# robot.net
KiCad netlist of a schematic drawn in EAGLE
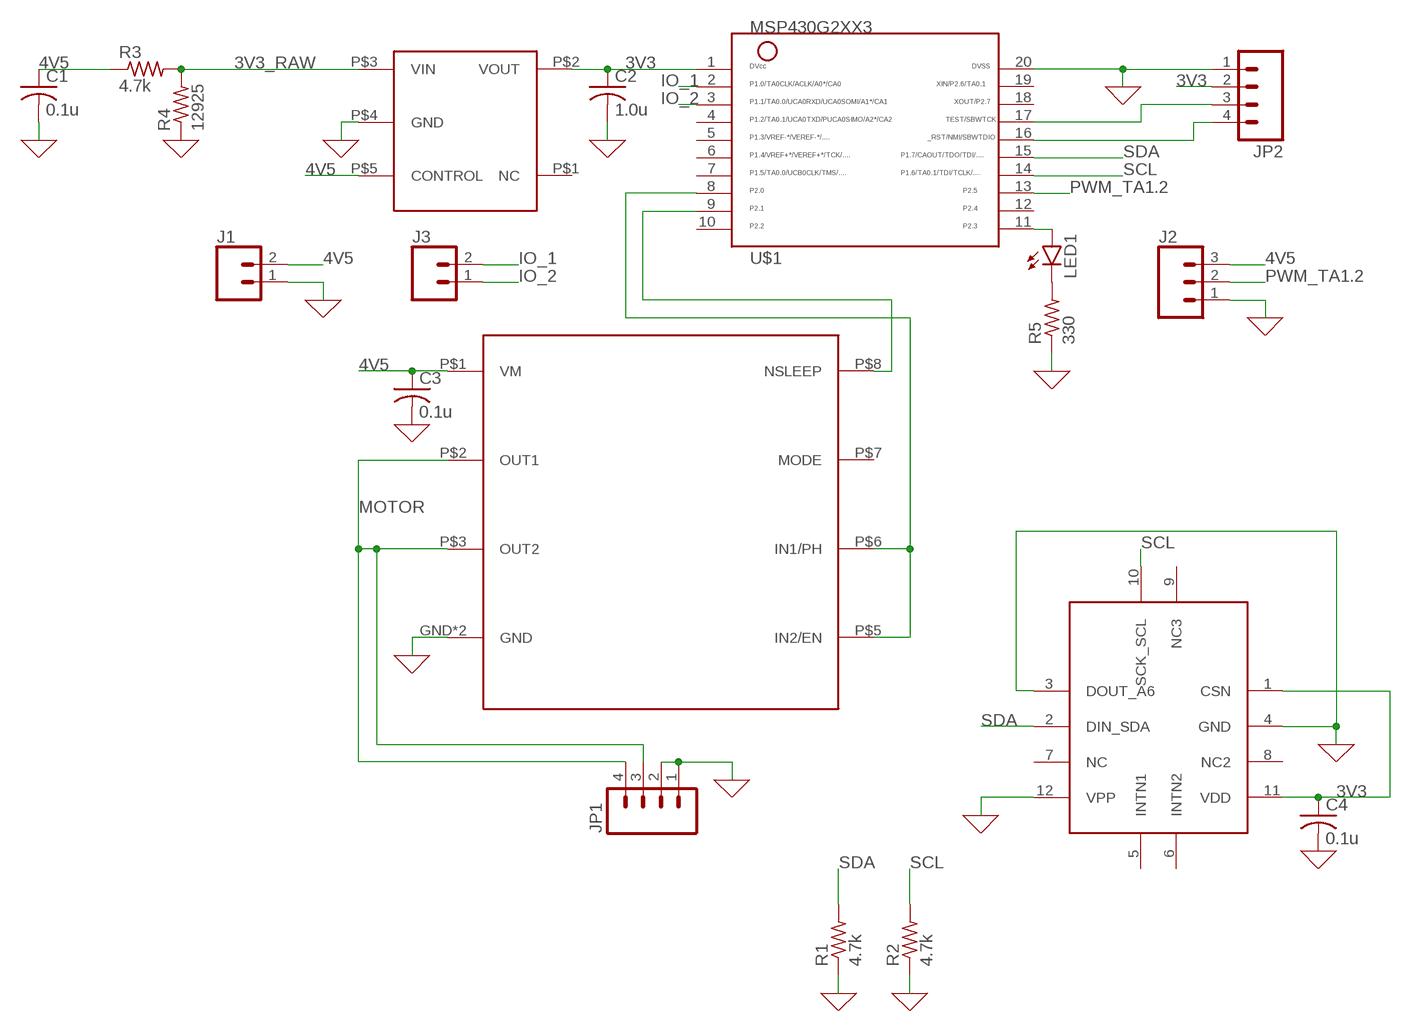
[diagram p0: schematic, sheet 1]

(export (version "E")
  (design (tool "Eeschema 10.0.6"))
  (components
    (comp (ref "C1")
      (value "0.1u")
      (footprint "eagle-import:C0805")
      (libsource (lib "eagle-import") (part "C-USC0805"))
    )
    (comp (ref "C2")
      (value "1.0u")
      (footprint "eagle-import:C0805")
      (libsource (lib "eagle-import") (part "C-USC0805"))
    )
    (comp (ref "C3")
      (value "0.1u")
      (footprint "eagle-import:C0805")
      (libsource (lib "eagle-import") (part "C-USC0805"))
    )
    (comp (ref "C4")
      (value "0.1u")
      (footprint "eagle-import:C0805")
      (libsource (lib "eagle-import") (part "C-USC0805"))
    )
    (comp (ref "J1")
      (value "CONN_02")
      (footprint "eagle-import:1X02")
      (libsource (lib "eagle-import") (part "CONN_02"))
    )
    (comp (ref "J2")
      (value "CONN_03LOCK")
      (footprint "eagle-import:1X03_LOCK")
      (libsource (lib "eagle-import") (part "CONN_03LOCK"))
    )
    (comp (ref "J3")
      (value "CONN_02")
      (footprint "eagle-import:1X02")
      (libsource (lib "eagle-import") (part "CONN_02"))
    )
    (comp (ref "JP1")
      (value "HEADER_1X04LOCK")
      (footprint "eagle-import:1X04_LOCK")
      (libsource (lib "eagle-import") (part "HEADER_1X04LOCK"))
    )
    (comp (ref "JP2")
      (value "HEADER_1X04LOCK")
      (footprint "eagle-import:1X04_LOCK")
      (libsource (lib "eagle-import") (part "HEADER_1X04LOCK"))
    )
    (comp (ref "LED1")
      (value "LED5MM")
      (footprint "eagle-import:LED5MM")
      (libsource (lib "eagle-import") (part "LED5MM"))
    )
    (comp (ref "R1")
      (value "4.7k")
      (footprint "eagle-import:R0805")
      (libsource (lib "eagle-import") (part "R-US_R0805"))
    )
    (comp (ref "R2")
      (value "4.7k")
      (footprint "eagle-import:R0805")
      (libsource (lib "eagle-import") (part "R-US_R0805"))
    )
    (comp (ref "R3")
      (value "4.7k")
      (footprint "eagle-import:R0805")
      (libsource (lib "eagle-import") (part "R-US_R0805"))
    )
    (comp (ref "R4")
      (value "12925")
      (footprint "eagle-import:R0805")
      (libsource (lib "eagle-import") (part "R-US_R0805"))
    )
    (comp (ref "R5")
      (value "330")
      (footprint "eagle-import:R0805")
      (libsource (lib "eagle-import") (part "R-US_R0805"))
    )
    (comp (ref "U$1")
      (value "MSP430G2XX3PDIP")
      (footprint "eagle-import:N20")
      (libsource (lib "eagle-import") (part "MSP430G2XX3PDIP"))
    )
    (comp (ref "U$2")
      (value "DRV8220_H_BRIDGE")
      (footprint "eagle-import:DRV8220_H_BRIDGE")
      (libsource (lib "eagle-import") (part "DRV8220_H_BRIDGE"))
    )
    (comp (ref "U$4")
      (value "TCR2EF3V3")
      (footprint "eagle-import:TCR2EF3V3")
      (libsource (lib "eagle-import") (part "TCR2EF3V3"))
    )
    (comp (ref "U$5")
      (value "MC3419VFLGA-12")
      (footprint "eagle-import:IC_MXC6655XA")
      (libsource (lib "eagle-import") (part "MC3419VFLGA-12"))
    )
  )
  (nets
    (net (code "1") (name "/3V3") (class "Default")
      (node (ref "C2") (pin "1") (pinfunction "1_1") (pintype "passive"))
      (node (ref "C4") (pin "1") (pinfunction "1_1") (pintype "passive"))
      (node (ref "JP2") (pin "2") (pinfunction "2_2") (pintype "passive"))
      (node (ref "U$1") (pin "1") (pinfunction "1_1") (pintype "bidirectional"))
      (node (ref "U$4") (pin "P$2") (pinfunction "VOUT_P$2") (pintype "passive"))
      (node (ref "U$5") (pin "1") (pinfunction "CSN_1") (pintype "passive"))
      (node (ref "U$5") (pin "11") (pinfunction "VDD_11") (pintype "passive"))
    )
    (net (code "2") (name "/3V3_RAW") (class "Default")
      (node (ref "R3") (pin "2") (pinfunction "2_2") (pintype "passive"))
      (node (ref "R4") (pin "2") (pinfunction "2_2") (pintype "passive"))
      (node (ref "U$4") (pin "P$3") (pinfunction "VIN_P$3") (pintype "passive"))
    )
    (net (code "3") (name "/4V5") (class "Default")
      (node (ref "C1") (pin "1") (pinfunction "1_1") (pintype "passive"))
      (node (ref "C3") (pin "1") (pinfunction "1_1") (pintype "passive"))
      (node (ref "J1") (pin "2") (pinfunction "2_2") (pintype "passive"))
      (node (ref "J2") (pin "3") (pinfunction "3_3") (pintype "passive"))
      (node (ref "R3") (pin "1") (pinfunction "1_1") (pintype "passive"))
      (node (ref "U$2") (pin "P$1") (pinfunction "VM_P$1") (pintype "passive"))
      (node (ref "U$4") (pin "P$5") (pinfunction "CONTROL_P$5") (pintype "passive"))
    )
    (net (code "4") (name "/IO_1") (class "Default")
      (node (ref "J3") (pin "2") (pinfunction "2_2") (pintype "passive"))
      (node (ref "U$1") (pin "2") (pinfunction "2_2") (pintype "bidirectional"))
    )
    (net (code "5") (name "/IO_2") (class "Default")
      (node (ref "J3") (pin "1") (pinfunction "1_1") (pintype "passive"))
      (node (ref "U$1") (pin "3") (pinfunction "3_3") (pintype "bidirectional"))
    )
    (net (code "6") (name "/MOTOR") (class "Default")
      (node (ref "JP1") (pin "3") (pinfunction "3_3") (pintype "passive"))
      (node (ref "JP1") (pin "4") (pinfunction "4_4") (pintype "passive"))
      (node (ref "U$2") (pin "P$2") (pinfunction "OUT1_P$2") (pintype "passive"))
      (node (ref "U$2") (pin "P$3") (pinfunction "OUT2_P$3") (pintype "passive"))
    )
    (net (code "7") (name "/PWM_TA1.2") (class "Default")
      (node (ref "J2") (pin "2") (pinfunction "2_2") (pintype "passive"))
      (node (ref "U$1") (pin "13") (pinfunction "13_13") (pintype "bidirectional"))
    )
    (net (code "8") (name "/SCL") (class "Default")
      (node (ref "R2") (pin "2") (pinfunction "2_2") (pintype "passive"))
      (node (ref "U$1") (pin "14") (pinfunction "14_14") (pintype "bidirectional"))
      (node (ref "U$5") (pin "10") (pinfunction "SCK_SCL_10") (pintype "passive"))
    )
    (net (code "9") (name "/SDA") (class "Default")
      (node (ref "R1") (pin "2") (pinfunction "2_2") (pintype "passive"))
      (node (ref "U$1") (pin "15") (pinfunction "15_15") (pintype "bidirectional"))
      (node (ref "U$5") (pin "2") (pinfunction "DIN_SDA_2") (pintype "passive"))
    )
    (net (code "10") (name "GND") (class "Default")
      (node (ref "C1") (pin "2") (pinfunction "2_2") (pintype "passive"))
      (node (ref "C2") (pin "2") (pinfunction "2_2") (pintype "passive"))
      (node (ref "C3") (pin "2") (pinfunction "2_2") (pintype "passive"))
      (node (ref "C4") (pin "2") (pinfunction "2_2") (pintype "passive"))
      (node (ref "J1") (pin "1") (pinfunction "1_1") (pintype "passive"))
      (node (ref "J2") (pin "1") (pinfunction "1_1") (pintype "passive"))
      (node (ref "JP1") (pin "1") (pinfunction "1_1") (pintype "passive"))
      (node (ref "JP1") (pin "2") (pinfunction "2_2") (pintype "passive"))
      (node (ref "JP2") (pin "1") (pinfunction "1_1") (pintype "passive"))
      (node (ref "R1") (pin "1") (pinfunction "1_1") (pintype "passive"))
      (node (ref "R2") (pin "1") (pinfunction "1_1") (pintype "passive"))
      (node (ref "R4") (pin "1") (pinfunction "1_1") (pintype "passive"))
      (node (ref "R5") (pin "1") (pinfunction "1_1") (pintype "passive"))
      (node (ref "U$1") (pin "20") (pinfunction "20_20") (pintype "bidirectional"))
      (node (ref "U$2") (pin "GND") (pinfunction "GND_GND") (pintype "passive"))
      (node (ref "U$2") (pin "P$4") (pinfunction "GND_P$4") (pintype "passive"))
      (node (ref "U$4") (pin "P$4") (pinfunction "GND_P$4") (pintype "passive"))
      (node (ref "U$5") (pin "12") (pinfunction "VPP_12") (pintype "passive"))
      (node (ref "U$5") (pin "3") (pinfunction "DOUT_A6_3") (pintype "passive"))
      (node (ref "U$5") (pin "4") (pinfunction "GND_4") (pintype "passive"))
    )
    (net (code "11") (name "Net-(JP2-Pad3)") (class "Default")
      (node (ref "JP2") (pin "3") (pinfunction "3_3") (pintype "passive"))
      (node (ref "U$1") (pin "17") (pinfunction "17_17") (pintype "bidirectional"))
    )
    (net (code "12") (name "Net-(JP2-Pad4)") (class "Default")
      (node (ref "JP2") (pin "4") (pinfunction "4_4") (pintype "passive"))
      (node (ref "U$1") (pin "16") (pinfunction "16_16") (pintype "bidirectional"))
    )
    (net (code "13") (name "Net-(LED1-C)") (class "Default")
      (node (ref "LED1") (pin "K") (pinfunction "C_K") (pintype "passive"))
      (node (ref "R5") (pin "2") (pinfunction "2_2") (pintype "passive"))
    )
    (net (code "14") (name "Net-(LED1-PadA)") (class "Default")
      (node (ref "LED1") (pin "A") (pinfunction "A_A") (pintype "passive"))
      (node (ref "U$1") (pin "11") (pinfunction "11_11") (pintype "bidirectional"))
    )
    (net (code "15") (name "Net-(U$2-IN1{slash}PH)") (class "Default")
      (node (ref "U$1") (pin "8") (pinfunction "8_8") (pintype "bidirectional"))
      (node (ref "U$2") (pin "P$5") (pinfunction "IN2/EN_P$5") (pintype "passive"))
      (node (ref "U$2") (pin "P$6") (pinfunction "IN1/PH_P$6") (pintype "passive"))
    )
    (net (code "16") (name "Net-(U$2-NSLEEP)") (class "Default")
      (node (ref "U$1") (pin "9") (pinfunction "9_9") (pintype "bidirectional"))
      (node (ref "U$2") (pin "P$8") (pinfunction "NSLEEP_P$8") (pintype "passive"))
    )
    (net (code "17") (name "unconnected-(U$1-Pad4)") (class "Default")
      (node (ref "U$1") (pin "4") (pinfunction "4_4") (pintype "bidirectional"))
    )
    (net (code "18") (name "unconnected-(U$1-Pad5)") (class "Default")
      (node (ref "U$1") (pin "5") (pinfunction "5_5") (pintype "bidirectional"))
    )
    (net (code "19") (name "unconnected-(U$1-Pad6)") (class "Default")
      (node (ref "U$1") (pin "6") (pinfunction "6_6") (pintype "bidirectional"))
    )
    (net (code "20") (name "unconnected-(U$1-Pad7)") (class "Default")
      (node (ref "U$1") (pin "7") (pinfunction "7_7") (pintype "bidirectional"))
    )
    (net (code "21") (name "unconnected-(U$1-Pad10)") (class "Default")
      (node (ref "U$1") (pin "10") (pinfunction "10_10") (pintype "bidirectional"))
    )
    (net (code "22") (name "unconnected-(U$1-Pad12)") (class "Default")
      (node (ref "U$1") (pin "12") (pinfunction "12_12") (pintype "bidirectional"))
    )
    (net (code "23") (name "unconnected-(U$1-Pad18)") (class "Default")
      (node (ref "U$1") (pin "18") (pinfunction "18_18") (pintype "bidirectional"))
    )
    (net (code "24") (name "unconnected-(U$1-Pad19)") (class "Default")
      (node (ref "U$1") (pin "19") (pinfunction "19_19") (pintype "bidirectional"))
    )
    (net (code "25") (name "unconnected-(U$2-MODE-PadP$7)") (class "Default")
      (node (ref "U$2") (pin "P$7") (pinfunction "MODE_P$7") (pintype "passive"))
    )
    (net (code "26") (name "unconnected-(U$4-NC-PadP$1)") (class "Default")
      (node (ref "U$4") (pin "P$1") (pinfunction "NC_P$1") (pintype "no_connect"))
    )
    (net (code "27") (name "unconnected-(U$5-INTN1-Pad5)") (class "Default")
      (node (ref "U$5") (pin "5") (pinfunction "INTN1_5") (pintype "passive"))
    )
    (net (code "28") (name "unconnected-(U$5-INTN2-Pad6)") (class "Default")
      (node (ref "U$5") (pin "6") (pinfunction "INTN2_6") (pintype "passive"))
    )
    (net (code "29") (name "unconnected-(U$5-NC-Pad7)") (class "Default")
      (node (ref "U$5") (pin "7") (pinfunction "NC_7") (pintype "passive"))
    )
    (net (code "30") (name "unconnected-(U$5-NC2-Pad8)") (class "Default")
      (node (ref "U$5") (pin "8") (pinfunction "NC2_8") (pintype "no_connect"))
    )
    (net (code "31") (name "unconnected-(U$5-NC3-Pad9)") (class "Default")
      (node (ref "U$5") (pin "9") (pinfunction "NC3_9") (pintype "no_connect"))
    )
  )
)
